# 04_-_CPU_IO.net
KiCad netlist of a schematic drawn in Altium Designer
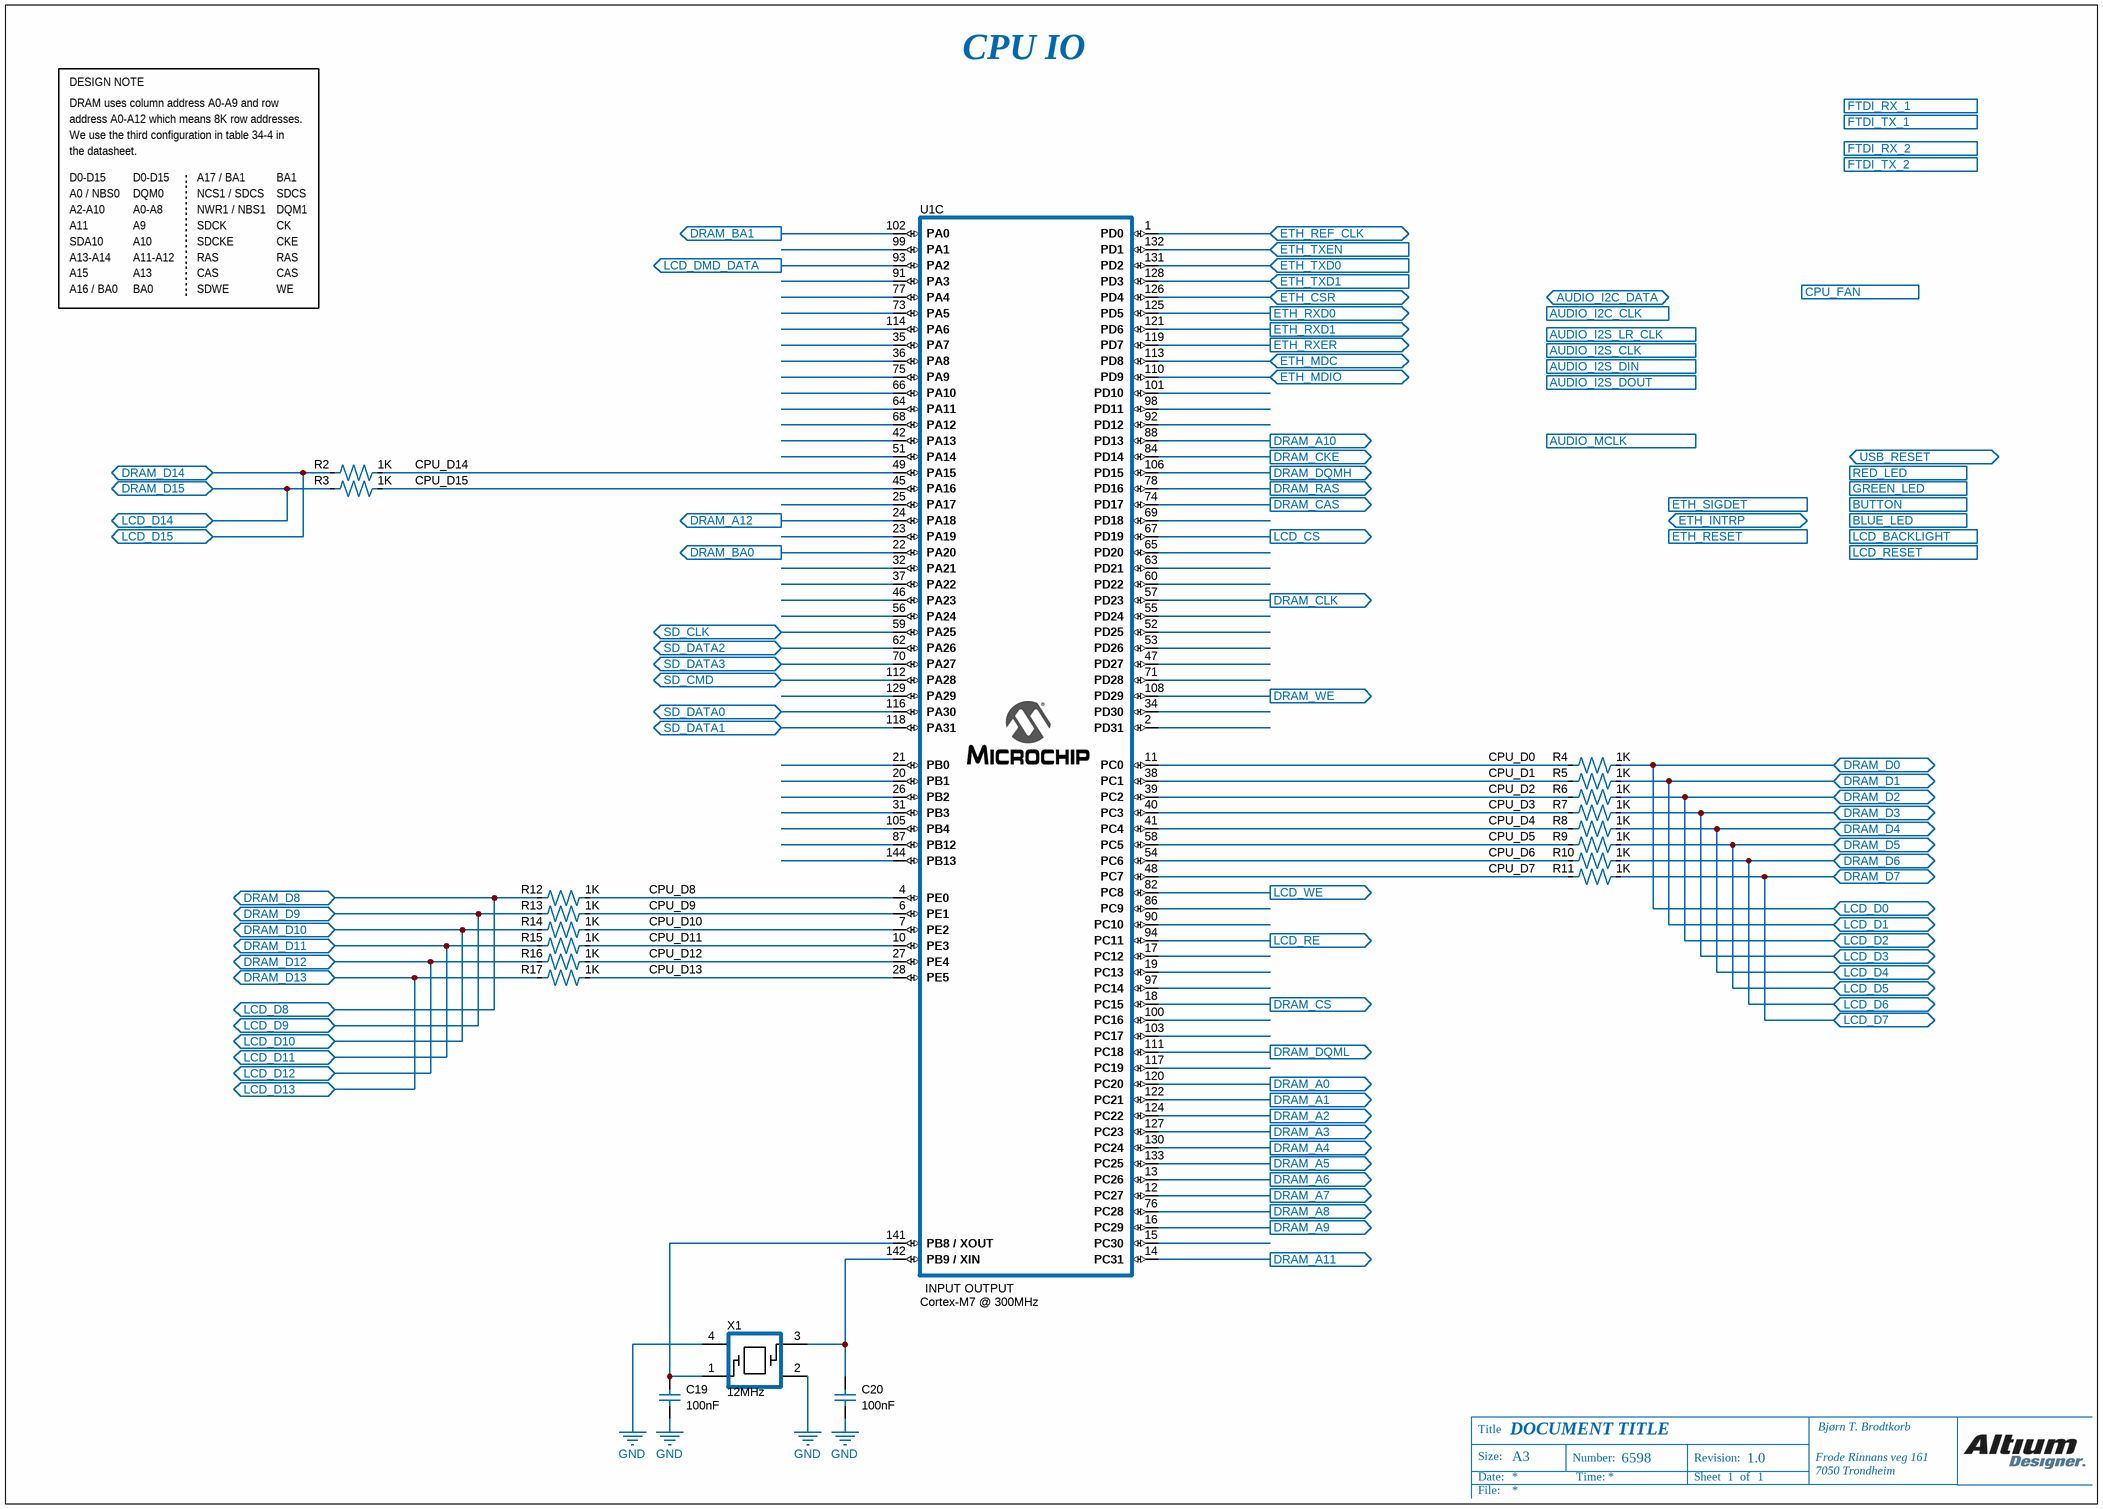
[diagram p0: [04] - CPU IO.SchDoc]

(export (version "E")
  (design (tool "Eeschema 10.0.6"))
  (components
    (comp (ref "C19")
      (value "100nF")
      (footprint "C0402")
      (description "C0402")
      (fields (field (name "Comment") "04023C103KAT2A"))
      (libsource (lib "Passive components") (part "04023C103KAT2A"))
    )
    (comp (ref "C20")
      (value "100nF")
      (footprint "C0402")
      (description "C0402")
      (fields (field (name "Comment") "04023C103KAT2A"))
      (libsource (lib "Passive components") (part "04023C103KAT2A"))
    )
    (comp (ref "R2")
      (value "1K")
      (footprint "R0402")
      (description "R0402")
      (fields (field (name "Comment") "CRCW04020000Z0ED"))
      (libsource (lib "Passive components") (part "CRCW04020000Z0ED"))
    )
    (comp (ref "R3")
      (value "1K")
      (footprint "R0402")
      (description "R0402")
      (fields (field (name "Comment") "CRCW04020000Z0ED"))
      (libsource (lib "Passive components") (part "CRCW04020000Z0ED"))
    )
    (comp (ref "R4")
      (value "1K")
      (footprint "R0402")
      (description "R0402")
      (fields (field (name "Comment") "CRCW04020000Z0ED"))
      (libsource (lib "Passive components") (part "CRCW04020000Z0ED"))
    )
    (comp (ref "R5")
      (value "1K")
      (footprint "R0402")
      (description "R0402")
      (fields (field (name "Comment") "CRCW04020000Z0ED"))
      (libsource (lib "Passive components") (part "CRCW04020000Z0ED"))
    )
    (comp (ref "R6")
      (value "1K")
      (footprint "R0402")
      (description "R0402")
      (fields (field (name "Comment") "CRCW04020000Z0ED"))
      (libsource (lib "Passive components") (part "CRCW04020000Z0ED"))
    )
    (comp (ref "R7")
      (value "1K")
      (footprint "R0402")
      (description "R0402")
      (fields (field (name "Comment") "CRCW04020000Z0ED"))
      (libsource (lib "Passive components") (part "CRCW04020000Z0ED"))
    )
    (comp (ref "R8")
      (value "1K")
      (footprint "R0402")
      (description "R0402")
      (fields (field (name "Comment") "CRCW04020000Z0ED"))
      (libsource (lib "Passive components") (part "CRCW04020000Z0ED"))
    )
    (comp (ref "R9")
      (value "1K")
      (footprint "R0402")
      (description "R0402")
      (fields (field (name "Comment") "CRCW04020000Z0ED"))
      (libsource (lib "Passive components") (part "CRCW04020000Z0ED"))
    )
    (comp (ref "R10")
      (value "1K")
      (footprint "R0402")
      (description "R0402")
      (fields (field (name "Comment") "CRCW04020000Z0ED"))
      (libsource (lib "Passive components") (part "CRCW04020000Z0ED"))
    )
    (comp (ref "R11")
      (value "1K")
      (footprint "R0402")
      (description "R0402")
      (fields (field (name "Comment") "CRCW04020000Z0ED"))
      (libsource (lib "Passive components") (part "CRCW04020000Z0ED"))
    )
    (comp (ref "R12")
      (value "1K")
      (footprint "R0402")
      (description "R0402")
      (fields (field (name "Comment") "CRCW04020000Z0ED"))
      (libsource (lib "Passive components") (part "CRCW04020000Z0ED"))
    )
    (comp (ref "R13")
      (value "1K")
      (footprint "R0402")
      (description "R0402")
      (fields (field (name "Comment") "CRCW04020000Z0ED"))
      (libsource (lib "Passive components") (part "CRCW04020000Z0ED"))
    )
    (comp (ref "R14")
      (value "1K")
      (footprint "R0402")
      (description "R0402")
      (fields (field (name "Comment") "CRCW04020000Z0ED"))
      (libsource (lib "Passive components") (part "CRCW04020000Z0ED"))
    )
    (comp (ref "R15")
      (value "1K")
      (footprint "R0402")
      (description "R0402")
      (fields (field (name "Comment") "CRCW04020000Z0ED"))
      (libsource (lib "Passive components") (part "CRCW04020000Z0ED"))
    )
    (comp (ref "R16")
      (value "1K")
      (footprint "R0402")
      (description "R0402")
      (fields (field (name "Comment") "CRCW04020000Z0ED"))
      (libsource (lib "Passive components") (part "CRCW04020000Z0ED"))
    )
    (comp (ref "R17")
      (value "1K")
      (footprint "R0402")
      (description "R0402")
      (fields (field (name "Comment") "CRCW04020000Z0ED"))
      (libsource (lib "Passive components") (part "CRCW04020000Z0ED"))
    )
    (comp (ref "U1")
      (value "Cortex-M7 @ 300MHz")
      (footprint "ATSAMS70Q21A-AN")
      (description "ATSAMS70Q21")
      (libsource (lib "Microcontrollers") (part "ATSAMS70Q21A-AN"))
    )
    (comp (ref "X1")
      (value "12MHz")
      (footprint "MCSJK-7U-12.00-12-30-80-B-30")
      (description "Crystal 12MHz 3.2mm x 2.5mm")
      (libsource (lib "Crystals") (part "MCSJK-7U-12.00-12-30-80-B-30"))
    )
  )
  (nets
    (net (code "10") (name "/CPU_D0") (class "Default")
      (node (ref "R4") (pin "2") (pinfunction "3_2") (pintype "passive"))
      (node (ref "U1") (pin "11") (pinfunction "PC0_11") (pintype "bidirectional"))
    )
    (net (code "11") (name "/CPU_D1") (class "Default")
      (node (ref "R5") (pin "2") (pinfunction "3_2") (pintype "passive"))
      (node (ref "U1") (pin "38") (pinfunction "PC1_38") (pintype "bidirectional"))
    )
    (net (code "12") (name "/CPU_D2") (class "Default")
      (node (ref "R6") (pin "2") (pinfunction "3_2") (pintype "passive"))
      (node (ref "U1") (pin "39") (pinfunction "PC2_39") (pintype "bidirectional"))
    )
    (net (code "13") (name "/CPU_D3") (class "Default")
      (node (ref "R7") (pin "2") (pinfunction "3_2") (pintype "passive"))
      (node (ref "U1") (pin "40") (pinfunction "PC3_40") (pintype "bidirectional"))
    )
    (net (code "14") (name "/CPU_D4") (class "Default")
      (node (ref "R8") (pin "2") (pinfunction "3_2") (pintype "passive"))
      (node (ref "U1") (pin "41") (pinfunction "PC4_41") (pintype "bidirectional"))
    )
    (net (code "15") (name "/CPU_D5") (class "Default")
      (node (ref "R9") (pin "2") (pinfunction "3_2") (pintype "passive"))
      (node (ref "U1") (pin "58") (pinfunction "PC5_58") (pintype "bidirectional"))
    )
    (net (code "16") (name "/CPU_D6") (class "Default")
      (node (ref "R10") (pin "2") (pinfunction "3_2") (pintype "passive"))
      (node (ref "U1") (pin "54") (pinfunction "PC6_54") (pintype "bidirectional"))
    )
    (net (code "17") (name "/CPU_D7") (class "Default")
      (node (ref "R11") (pin "2") (pinfunction "3_2") (pintype "passive"))
      (node (ref "U1") (pin "48") (pinfunction "PC7_48") (pintype "bidirectional"))
    )
    (net (code "18") (name "/CPU_D8") (class "Default")
      (node (ref "R12") (pin "1") (pinfunction "1_1") (pintype "passive"))
      (node (ref "U1") (pin "4") (pinfunction "PE0_4") (pintype "bidirectional"))
    )
    (net (code "19") (name "/CPU_D9") (class "Default")
      (node (ref "R13") (pin "1") (pinfunction "1_1") (pintype "passive"))
      (node (ref "U1") (pin "6") (pinfunction "PE1_6") (pintype "bidirectional"))
    )
    (net (code "20") (name "/CPU_D10") (class "Default")
      (node (ref "R14") (pin "1") (pinfunction "1_1") (pintype "passive"))
      (node (ref "U1") (pin "7") (pinfunction "PE2_7") (pintype "bidirectional"))
    )
    (net (code "21") (name "/CPU_D11") (class "Default")
      (node (ref "R15") (pin "1") (pinfunction "1_1") (pintype "passive"))
      (node (ref "U1") (pin "10") (pinfunction "PE3_10") (pintype "bidirectional"))
    )
    (net (code "22") (name "/CPU_D12") (class "Default")
      (node (ref "R16") (pin "1") (pinfunction "1_1") (pintype "passive"))
      (node (ref "U1") (pin "27") (pinfunction "PE4_27") (pintype "bidirectional"))
    )
    (net (code "23") (name "/CPU_D13") (class "Default")
      (node (ref "R17") (pin "1") (pinfunction "1_1") (pintype "passive"))
      (node (ref "U1") (pin "28") (pinfunction "PE5_28") (pintype "bidirectional"))
    )
    (net (code "24") (name "/CPU_D14") (class "Default")
      (node (ref "R2") (pin "1") (pinfunction "1_1") (pintype "passive"))
      (node (ref "U1") (pin "49") (pinfunction "PA15_49") (pintype "bidirectional"))
    )
    (net (code "25") (name "/CPU_D15") (class "Default")
      (node (ref "R3") (pin "1") (pinfunction "1_1") (pintype "passive"))
      (node (ref "U1") (pin "45") (pinfunction "PA16_45") (pintype "bidirectional"))
    )
    (net (code "27") (name "/DRAM_A0") (class "Default")
      (node (ref "U1") (pin "120") (pinfunction "PC20_120") (pintype "bidirectional"))
    )
    (net (code "28") (name "/DRAM_A1") (class "Default")
      (node (ref "U1") (pin "122") (pinfunction "PC21_122") (pintype "bidirectional"))
    )
    (net (code "29") (name "/DRAM_A2") (class "Default")
      (node (ref "U1") (pin "124") (pinfunction "PC22_124") (pintype "bidirectional"))
    )
    (net (code "30") (name "/DRAM_A3") (class "Default")
      (node (ref "U1") (pin "127") (pinfunction "PC23_127") (pintype "bidirectional"))
    )
    (net (code "31") (name "/DRAM_A4") (class "Default")
      (node (ref "U1") (pin "130") (pinfunction "PC24_130") (pintype "bidirectional"))
    )
    (net (code "32") (name "/DRAM_A5") (class "Default")
      (node (ref "U1") (pin "133") (pinfunction "PC25_133") (pintype "bidirectional"))
    )
    (net (code "33") (name "/DRAM_A6") (class "Default")
      (node (ref "U1") (pin "13") (pinfunction "PC26_13") (pintype "bidirectional"))
    )
    (net (code "34") (name "/DRAM_A7") (class "Default")
      (node (ref "U1") (pin "12") (pinfunction "PC27_12") (pintype "bidirectional"))
    )
    (net (code "35") (name "/DRAM_A8") (class "Default")
      (node (ref "U1") (pin "76") (pinfunction "PC28_76") (pintype "bidirectional"))
    )
    (net (code "36") (name "/DRAM_A9") (class "Default")
      (node (ref "U1") (pin "16") (pinfunction "PC29_16") (pintype "bidirectional"))
    )
    (net (code "37") (name "/DRAM_A10") (class "Default")
      (node (ref "U1") (pin "88") (pinfunction "PD13_88") (pintype "bidirectional"))
    )
    (net (code "38") (name "/DRAM_A11") (class "Default")
      (node (ref "U1") (pin "14") (pinfunction "PC31_14") (pintype "bidirectional"))
    )
    (net (code "39") (name "/DRAM_A12") (class "Default")
      (node (ref "U1") (pin "24") (pinfunction "PA18_24") (pintype "bidirectional"))
    )
    (net (code "40") (name "/DRAM_BA0") (class "Default")
      (node (ref "U1") (pin "22") (pinfunction "PA20_22") (pintype "bidirectional"))
    )
    (net (code "41") (name "/DRAM_BA1") (class "Default")
      (node (ref "U1") (pin "102") (pinfunction "PA0_102") (pintype "bidirectional"))
    )
    (net (code "42") (name "/DRAM_CAS") (class "Default")
      (node (ref "U1") (pin "74") (pinfunction "PD17_74") (pintype "bidirectional"))
    )
    (net (code "43") (name "/DRAM_CKE") (class "Default")
      (node (ref "U1") (pin "84") (pinfunction "PD14_84") (pintype "bidirectional"))
    )
    (net (code "44") (name "/DRAM_CLK") (class "Default")
      (node (ref "U1") (pin "57") (pinfunction "PD23_57") (pintype "bidirectional"))
    )
    (net (code "45") (name "/DRAM_CS") (class "Default")
      (node (ref "U1") (pin "18") (pinfunction "PC15_18") (pintype "bidirectional"))
    )
    (net (code "46") (name "/DRAM_D0") (class "Default")
      (node (ref "R4") (pin "1") (pinfunction "1_1") (pintype "passive"))
    )
    (net (code "47") (name "/DRAM_D1") (class "Default")
      (node (ref "R5") (pin "1") (pinfunction "1_1") (pintype "passive"))
    )
    (net (code "48") (name "/DRAM_D2") (class "Default")
      (node (ref "R6") (pin "1") (pinfunction "1_1") (pintype "passive"))
    )
    (net (code "49") (name "/DRAM_D3") (class "Default")
      (node (ref "R7") (pin "1") (pinfunction "1_1") (pintype "passive"))
    )
    (net (code "50") (name "/DRAM_D4") (class "Default")
      (node (ref "R8") (pin "1") (pinfunction "1_1") (pintype "passive"))
    )
    (net (code "51") (name "/DRAM_D5") (class "Default")
      (node (ref "R9") (pin "1") (pinfunction "1_1") (pintype "passive"))
    )
    (net (code "52") (name "/DRAM_D6") (class "Default")
      (node (ref "R10") (pin "1") (pinfunction "1_1") (pintype "passive"))
    )
    (net (code "53") (name "/DRAM_D7") (class "Default")
      (node (ref "R11") (pin "1") (pinfunction "1_1") (pintype "passive"))
    )
    (net (code "54") (name "/DRAM_D8") (class "Default")
      (node (ref "R12") (pin "2") (pinfunction "3_2") (pintype "passive"))
    )
    (net (code "55") (name "/DRAM_D9") (class "Default")
      (node (ref "R13") (pin "2") (pinfunction "3_2") (pintype "passive"))
    )
    (net (code "56") (name "/DRAM_D10") (class "Default")
      (node (ref "R14") (pin "2") (pinfunction "3_2") (pintype "passive"))
    )
    (net (code "57") (name "/DRAM_D11") (class "Default")
      (node (ref "R15") (pin "2") (pinfunction "3_2") (pintype "passive"))
    )
    (net (code "58") (name "/DRAM_D12") (class "Default")
      (node (ref "R16") (pin "2") (pinfunction "3_2") (pintype "passive"))
    )
    (net (code "59") (name "/DRAM_D13") (class "Default")
      (node (ref "R17") (pin "2") (pinfunction "3_2") (pintype "passive"))
    )
    (net (code "60") (name "/DRAM_D14") (class "Default")
      (node (ref "R2") (pin "2") (pinfunction "3_2") (pintype "passive"))
    )
    (net (code "61") (name "/DRAM_D15") (class "Default")
      (node (ref "R3") (pin "2") (pinfunction "3_2") (pintype "passive"))
    )
    (net (code "62") (name "/DRAM_DQMH") (class "Default")
      (node (ref "U1") (pin "106") (pinfunction "PD15_106") (pintype "bidirectional"))
    )
    (net (code "63") (name "/DRAM_DQML") (class "Default")
      (node (ref "U1") (pin "111") (pinfunction "PC18_111") (pintype "bidirectional"))
    )
    (net (code "64") (name "/DRAM_RAS") (class "Default")
      (node (ref "U1") (pin "78") (pinfunction "PD16_78") (pintype "bidirectional"))
    )
    (net (code "65") (name "/DRAM_WE") (class "Default")
      (node (ref "U1") (pin "108") (pinfunction "PD29_108") (pintype "bidirectional"))
    )
    (net (code "66") (name "/ETH_CSR") (class "Default")
      (node (ref "U1") (pin "126") (pinfunction "PD4_126") (pintype "bidirectional"))
    )
    (net (code "68") (name "/ETH_MDC") (class "Default")
      (node (ref "U1") (pin "113") (pinfunction "PD8_113") (pintype "bidirectional"))
    )
    (net (code "69") (name "/ETH_MDIO") (class "Default")
      (node (ref "U1") (pin "110") (pinfunction "PD9_110") (pintype "bidirectional"))
    )
    (net (code "70") (name "/ETH_REF_CLK") (class "Default")
      (node (ref "U1") (pin "1") (pinfunction "PD0_1") (pintype "bidirectional"))
    )
    (net (code "72") (name "/ETH_RXD0") (class "Default")
      (node (ref "U1") (pin "125") (pinfunction "PD5_125") (pintype "bidirectional"))
    )
    (net (code "73") (name "/ETH_RXD1") (class "Default")
      (node (ref "U1") (pin "121") (pinfunction "PD6_121") (pintype "bidirectional"))
    )
    (net (code "74") (name "/ETH_RXER") (class "Default")
      (node (ref "U1") (pin "119") (pinfunction "PD7_119") (pintype "bidirectional"))
    )
    (net (code "76") (name "/ETH_TXD0") (class "Default")
      (node (ref "U1") (pin "131") (pinfunction "PD2_131") (pintype "bidirectional"))
    )
    (net (code "77") (name "/ETH_TXD1") (class "Default")
      (node (ref "U1") (pin "128") (pinfunction "PD3_128") (pintype "bidirectional"))
    )
    (net (code "78") (name "/ETH_TXEN") (class "Default")
      (node (ref "U1") (pin "132") (pinfunction "PD1_132") (pintype "bidirectional"))
    )
    (net (code "85") (name "/LCD_CS") (class "Default")
      (node (ref "U1") (pin "67") (pinfunction "PD19_67") (pintype "bidirectional"))
    )
    (net (code "86") (name "/LCD_DMD_DATA") (class "Default")
      (node (ref "U1") (pin "93") (pinfunction "PA2_93") (pintype "bidirectional"))
    )
    (net (code "87") (name "/LCD_RE") (class "Default")
      (node (ref "U1") (pin "94") (pinfunction "PC11_94") (pintype "bidirectional"))
    )
    (net (code "89") (name "/LCD_WE") (class "Default")
      (node (ref "U1") (pin "82") (pinfunction "PC8_82") (pintype "bidirectional"))
    )
    (net (code "91") (name "/SD_CLK") (class "Default")
      (node (ref "U1") (pin "59") (pinfunction "PA25_59") (pintype "bidirectional"))
    )
    (net (code "92") (name "/SD_CMD") (class "Default")
      (node (ref "U1") (pin "112") (pinfunction "PA28_112") (pintype "bidirectional"))
    )
    (net (code "93") (name "/SD_DATA0") (class "Default")
      (node (ref "U1") (pin "116") (pinfunction "PA30_116") (pintype "bidirectional"))
    )
    (net (code "94") (name "/SD_DATA1") (class "Default")
      (node (ref "U1") (pin "118") (pinfunction "PA31_118") (pintype "bidirectional"))
    )
    (net (code "95") (name "/SD_DATA2") (class "Default")
      (node (ref "U1") (pin "62") (pinfunction "PA26_62") (pintype "bidirectional"))
    )
    (net (code "96") (name "/SD_DATA3") (class "Default")
      (node (ref "U1") (pin "70") (pinfunction "PA27_70") (pintype "bidirectional"))
    )
    (net (code "98") (name "GND") (class "Default")
      (node (ref "C19") (pin "1") (pinfunction "1_1") (pintype "passive"))
      (node (ref "C20") (pin "1") (pinfunction "1_1") (pintype "passive"))
      (node (ref "X1") (pin "2") (pinfunction "2_2") (pintype "passive"))
      (node (ref "X1") (pin "4") (pinfunction "4_4") (pintype "passive"))
    )
    (net (code "99") (name "Net-(U1C-PB8_{slash}_XOUT)") (class "Default")
      (node (ref "C19") (pin "2") (pinfunction "2_2") (pintype "passive"))
      (node (ref "U1") (pin "141") (pinfunction "PB8_/_XOUT_141") (pintype "bidirectional"))
      (node (ref "X1") (pin "1") (pinfunction "2_1") (pintype "passive"))
    )
    (net (code "100") (name "Net-(U1C-PB9_{slash}_XIN)") (class "Default")
      (node (ref "C20") (pin "2") (pinfunction "2_2") (pintype "passive"))
      (node (ref "U1") (pin "142") (pinfunction "PB9_/_XIN_142") (pintype "bidirectional"))
      (node (ref "X1") (pin "3") (pinfunction "2_3") (pintype "passive"))
    )
    (net (code "101") (name "unconnected-(U1C-PA1-Pad99)") (class "Default")
      (node (ref "U1") (pin "99") (pinfunction "PA1_99") (pintype "bidirectional"))
    )
    (net (code "102") (name "unconnected-(U1C-PA3-Pad91)") (class "Default")
      (node (ref "U1") (pin "91") (pinfunction "PA3_91") (pintype "bidirectional"))
    )
    (net (code "103") (name "unconnected-(U1C-PA4-Pad77)") (class "Default")
      (node (ref "U1") (pin "77") (pinfunction "PA4_77") (pintype "bidirectional"))
    )
    (net (code "104") (name "unconnected-(U1C-PA5-Pad73)") (class "Default")
      (node (ref "U1") (pin "73") (pinfunction "PA5_73") (pintype "bidirectional"))
    )
    (net (code "105") (name "unconnected-(U1C-PA6-Pad114)") (class "Default")
      (node (ref "U1") (pin "114") (pinfunction "PA6_114") (pintype "bidirectional"))
    )
    (net (code "106") (name "unconnected-(U1C-PA7-Pad35)") (class "Default")
      (node (ref "U1") (pin "35") (pinfunction "PA7_35") (pintype "bidirectional"))
    )
    (net (code "107") (name "unconnected-(U1C-PA8-Pad36)") (class "Default")
      (node (ref "U1") (pin "36") (pinfunction "PA8_36") (pintype "bidirectional"))
    )
    (net (code "108") (name "unconnected-(U1C-PA9-Pad75)") (class "Default")
      (node (ref "U1") (pin "75") (pinfunction "PA9_75") (pintype "bidirectional"))
    )
    (net (code "109") (name "unconnected-(U1C-PA10-Pad66)") (class "Default")
      (node (ref "U1") (pin "66") (pinfunction "PA10_66") (pintype "bidirectional"))
    )
    (net (code "110") (name "unconnected-(U1C-PA11-Pad64)") (class "Default")
      (node (ref "U1") (pin "64") (pinfunction "PA11_64") (pintype "bidirectional"))
    )
    (net (code "111") (name "unconnected-(U1C-PA12-Pad68)") (class "Default")
      (node (ref "U1") (pin "68") (pinfunction "PA12_68") (pintype "bidirectional"))
    )
    (net (code "112") (name "unconnected-(U1C-PA13-Pad42)") (class "Default")
      (node (ref "U1") (pin "42") (pinfunction "PA13_42") (pintype "bidirectional"))
    )
    (net (code "113") (name "unconnected-(U1C-PA14-Pad51)") (class "Default")
      (node (ref "U1") (pin "51") (pinfunction "PA14_51") (pintype "bidirectional"))
    )
    (net (code "114") (name "unconnected-(U1C-PA17-Pad25)") (class "Default")
      (node (ref "U1") (pin "25") (pinfunction "PA17_25") (pintype "bidirectional"))
    )
    (net (code "115") (name "unconnected-(U1C-PA19-Pad23)") (class "Default")
      (node (ref "U1") (pin "23") (pinfunction "PA19_23") (pintype "bidirectional"))
    )
    (net (code "116") (name "unconnected-(U1C-PA21-Pad32)") (class "Default")
      (node (ref "U1") (pin "32") (pinfunction "PA21_32") (pintype "bidirectional"))
    )
    (net (code "117") (name "unconnected-(U1C-PA22-Pad37)") (class "Default")
      (node (ref "U1") (pin "37") (pinfunction "PA22_37") (pintype "bidirectional"))
    )
    (net (code "118") (name "unconnected-(U1C-PA23-Pad46)") (class "Default")
      (node (ref "U1") (pin "46") (pinfunction "PA23_46") (pintype "bidirectional"))
    )
    (net (code "119") (name "unconnected-(U1C-PA24-Pad56)") (class "Default")
      (node (ref "U1") (pin "56") (pinfunction "PA24_56") (pintype "bidirectional"))
    )
    (net (code "120") (name "unconnected-(U1C-PA29-Pad129)") (class "Default")
      (node (ref "U1") (pin "129") (pinfunction "PA29_129") (pintype "bidirectional"))
    )
    (net (code "121") (name "unconnected-(U1C-PB0-Pad21)") (class "Default")
      (node (ref "U1") (pin "21") (pinfunction "PB0_21") (pintype "bidirectional"))
    )
    (net (code "122") (name "unconnected-(U1C-PB1-Pad20)") (class "Default")
      (node (ref "U1") (pin "20") (pinfunction "PB1_20") (pintype "bidirectional"))
    )
    (net (code "123") (name "unconnected-(U1C-PB2-Pad26)") (class "Default")
      (node (ref "U1") (pin "26") (pinfunction "PB2_26") (pintype "bidirectional"))
    )
    (net (code "124") (name "unconnected-(U1C-PB3-Pad31)") (class "Default")
      (node (ref "U1") (pin "31") (pinfunction "PB3_31") (pintype "bidirectional"))
    )
    (net (code "125") (name "unconnected-(U1C-PB4-Pad105)") (class "Default")
      (node (ref "U1") (pin "105") (pinfunction "PB4_105") (pintype "bidirectional"))
    )
    (net (code "126") (name "unconnected-(U1C-PB12-Pad87)") (class "Default")
      (node (ref "U1") (pin "87") (pinfunction "PB12_87") (pintype "bidirectional"))
    )
    (net (code "127") (name "unconnected-(U1C-PB13-Pad144)") (class "Default")
      (node (ref "U1") (pin "144") (pinfunction "PB13_144") (pintype "bidirectional"))
    )
    (net (code "128") (name "unconnected-(U1C-PC9-Pad86)") (class "Default")
      (node (ref "U1") (pin "86") (pinfunction "PC9_86") (pintype "bidirectional"))
    )
    (net (code "129") (name "unconnected-(U1C-PC10-Pad90)") (class "Default")
      (node (ref "U1") (pin "90") (pinfunction "PC10_90") (pintype "bidirectional"))
    )
    (net (code "130") (name "unconnected-(U1C-PC12-Pad17)") (class "Default")
      (node (ref "U1") (pin "17") (pinfunction "PC12_17") (pintype "bidirectional"))
    )
    (net (code "131") (name "unconnected-(U1C-PC13-Pad19)") (class "Default")
      (node (ref "U1") (pin "19") (pinfunction "PC13_19") (pintype "bidirectional"))
    )
    (net (code "132") (name "unconnected-(U1C-PC14-Pad97)") (class "Default")
      (node (ref "U1") (pin "97") (pinfunction "PC14_97") (pintype "bidirectional"))
    )
    (net (code "133") (name "unconnected-(U1C-PC16-Pad100)") (class "Default")
      (node (ref "U1") (pin "100") (pinfunction "PC16_100") (pintype "bidirectional"))
    )
    (net (code "134") (name "unconnected-(U1C-PC17-Pad103)") (class "Default")
      (node (ref "U1") (pin "103") (pinfunction "PC17_103") (pintype "bidirectional"))
    )
    (net (code "135") (name "unconnected-(U1C-PC19-Pad117)") (class "Default")
      (node (ref "U1") (pin "117") (pinfunction "PC19_117") (pintype "bidirectional"))
    )
    (net (code "136") (name "unconnected-(U1C-PC30-Pad15)") (class "Default")
      (node (ref "U1") (pin "15") (pinfunction "PC30_15") (pintype "bidirectional"))
    )
    (net (code "137") (name "unconnected-(U1C-PD10-Pad101)") (class "Default")
      (node (ref "U1") (pin "101") (pinfunction "PD10_101") (pintype "bidirectional"))
    )
    (net (code "138") (name "unconnected-(U1C-PD11-Pad98)") (class "Default")
      (node (ref "U1") (pin "98") (pinfunction "PD11_98") (pintype "bidirectional"))
    )
    (net (code "139") (name "unconnected-(U1C-PD12-Pad92)") (class "Default")
      (node (ref "U1") (pin "92") (pinfunction "PD12_92") (pintype "bidirectional"))
    )
    (net (code "140") (name "unconnected-(U1C-PD18-Pad69)") (class "Default")
      (node (ref "U1") (pin "69") (pinfunction "PD18_69") (pintype "bidirectional"))
    )
    (net (code "141") (name "unconnected-(U1C-PD20-Pad65)") (class "Default")
      (node (ref "U1") (pin "65") (pinfunction "PD20_65") (pintype "bidirectional"))
    )
    (net (code "142") (name "unconnected-(U1C-PD21-Pad63)") (class "Default")
      (node (ref "U1") (pin "63") (pinfunction "PD21_63") (pintype "bidirectional"))
    )
    (net (code "143") (name "unconnected-(U1C-PD22-Pad60)") (class "Default")
      (node (ref "U1") (pin "60") (pinfunction "PD22_60") (pintype "bidirectional"))
    )
    (net (code "144") (name "unconnected-(U1C-PD24-Pad55)") (class "Default")
      (node (ref "U1") (pin "55") (pinfunction "PD24_55") (pintype "bidirectional"))
    )
    (net (code "145") (name "unconnected-(U1C-PD25-Pad52)") (class "Default")
      (node (ref "U1") (pin "52") (pinfunction "PD25_52") (pintype "bidirectional"))
    )
    (net (code "146") (name "unconnected-(U1C-PD26-Pad53)") (class "Default")
      (node (ref "U1") (pin "53") (pinfunction "PD26_53") (pintype "bidirectional"))
    )
    (net (code "147") (name "unconnected-(U1C-PD27-Pad47)") (class "Default")
      (node (ref "U1") (pin "47") (pinfunction "PD27_47") (pintype "bidirectional"))
    )
    (net (code "148") (name "unconnected-(U1C-PD28-Pad71)") (class "Default")
      (node (ref "U1") (pin "71") (pinfunction "PD28_71") (pintype "bidirectional"))
    )
    (net (code "149") (name "unconnected-(U1C-PD30-Pad34)") (class "Default")
      (node (ref "U1") (pin "34") (pinfunction "PD30_34") (pintype "bidirectional"))
    )
    (net (code "150") (name "unconnected-(U1C-PD31-Pad2)") (class "Default")
      (node (ref "U1") (pin "2") (pinfunction "PD31_2") (pintype "bidirectional"))
    )
  )
)
